# Voice.net
KiCad netlist of a schematic drawn in Altium Designer
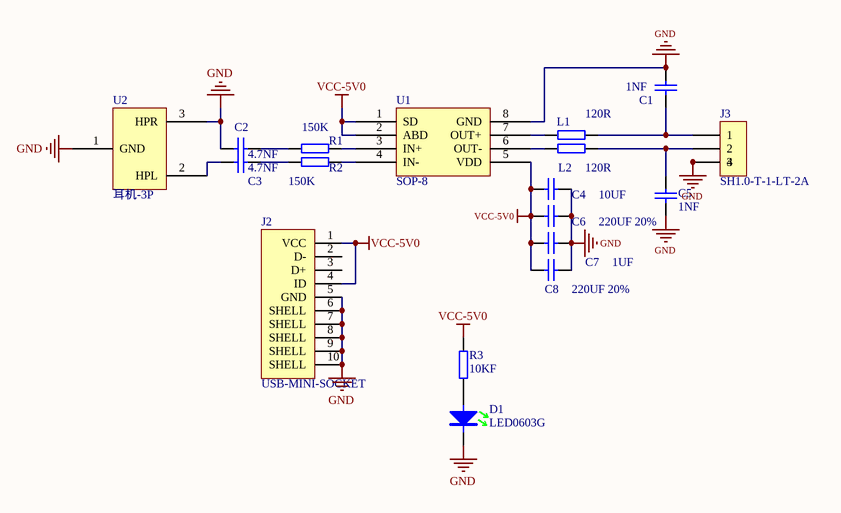
[diagram p0: Voice.SchDoc]

(export (version "E")
  (design (tool "Eeschema 10.0.6"))
  (components
    (comp (ref "C1")
      (value "1NF")
      (footprint "C0402")
      (description "贴片电容-陶瓷")
      (libsource (lib "Capacitor") (part "C0402X7R-220J10V"))
    )
    (comp (ref "C2")
      (value "4.7NF")
      (footprint "C0603")
      (description "贴片电容-陶瓷")
      (libsource (lib "Capacitor") (part "C0603X7R-330J25V"))
    )
    (comp (ref "C3")
      (value "4.7NF")
      (footprint "C0603")
      (description "贴片电容-陶瓷")
      (libsource (lib "Capacitor") (part "C0603X7R-330J25V"))
    )
    (comp (ref "C4")
      (value "10UF")
      (footprint "C0603")
      (description "贴片电容-陶瓷")
      (libsource (lib "Capacitor") (part "C0603X7R-330J25V"))
    )
    (comp (ref "C5")
      (value "1NF")
      (footprint "C0402")
      (description "贴片电容-陶瓷")
      (libsource (lib "Capacitor") (part "C0402X7R-220J10V"))
    )
    (comp (ref "C6")
      (value "220UF 20%")
      (footprint "C1206")
      (description "C 1206钽电容 --220UF 10V 3216 A型 有极性电容 3.2mm X 1.6mm")
      (libsource (lib "Capacitor") (part "C1206-A型 极性电容"))
    )
    (comp (ref "C7")
      (value "1UF")
      (footprint "C0402")
      (description "贴片电容-陶瓷")
      (libsource (lib "Capacitor") (part "C0402X7R-105J10V"))
    )
    (comp (ref "C8")
      (value "220UF 20%")
      (footprint "C1206")
      (description "C 1206钽电容 --220UF 10V 3216 A型 有极性电容 3.2mm X 1.6mm")
      (libsource (lib "Capacitor") (part "C1206-A型 极性电容"))
    )
    (comp (ref "D1")
      (value "LED0603G")
      (footprint "D-LED0603G")
      (description "贴片二极管-LED")
      (libsource (lib "PCB_Project_1") (part "DLED-0603-G"))
    )
    (comp (ref "J2")
      (value "USB-MINI-SOCKET")
      (footprint "MICRO-USB - 5.9")
      (description "USB-A卧式插座")
      (libsource (lib "PCB_Project_1") (part "J-USB-MINI-SOCKET"))
    )
    (comp (ref "J3")
      (value "SH1.0-T-1-LT-2A")
      (footprint "J-SH1.0-T-1-LT-2A")
      (description "接插件-SH1.0-T-1-LT-2A")
      (libsource (lib "Connector") (part "SH1.0-T-1-LT-2A"))
    )
    (comp (ref "L1")
      (value "120R")
      (footprint "R0603")
      (description "贴片电阻-通用")
      (libsource (lib "Resistor") (part "R0603-47KF"))
    )
    (comp (ref "L2")
      (value "120R")
      (footprint "R0603")
      (description "贴片电阻-通用")
      (libsource (lib "Resistor") (part "R0603-47KF"))
    )
    (comp (ref "R1")
      (value "150K")
      (footprint "R0603")
      (description "贴片电阻-通用")
      (libsource (lib "Resistor") (part "R0603-10KF"))
    )
    (comp (ref "R2")
      (value "150K")
      (footprint "R0603")
      (description "贴片电阻-通用")
      (libsource (lib "Resistor") (part "R0603-10KF"))
    )
    (comp (ref "R3")
      (value "10KF")
      (footprint "R0603")
      (description "贴片电阻-通用")
      (libsource (lib "PCB_Project_1") (part "R0603-10KF"))
    )
    (comp (ref "U1") (value "SOP-8") (footprint "SOP-8") (libsource (lib "PCB_Project_1") (part "CS8508E")))
    (comp (ref "U2") (value "耳机-3P") (footprint "耳机") (libsource (lib "PCB_Project_1") (part "耳机-3P")))
  )
  (nets
    (net (code "1") (name "GND") (class "Default")
      (node (ref "C1") (pin "2") (pinfunction "2_2") (pintype "passive"))
      (node (ref "C2") (pin "1") (pinfunction "1_1") (pintype "passive"))
      (node (ref "C4") (pin "2") (pinfunction "2_2") (pintype "passive"))
      (node (ref "C5") (pin "2") (pinfunction "2_2") (pintype "passive"))
      (node (ref "C6") (pin "1") (pinfunction "1_1") (pintype "passive"))
      (node (ref "C7") (pin "1") (pinfunction "1_1") (pintype "passive"))
      (node (ref "C8") (pin "1") (pinfunction "1_1") (pintype "passive"))
      (node (ref "D1") (pin "2") (pinfunction "2_2") (pintype "passive"))
      (node (ref "J2") (pin "10") (pinfunction "SHELL_10") (pintype "passive"))
      (node (ref "J2") (pin "5") (pinfunction "GND_5") (pintype "passive"))
      (node (ref "J2") (pin "6") (pinfunction "SHELL_6") (pintype "passive"))
      (node (ref "J2") (pin "7") (pinfunction "SHELL_7") (pintype "passive"))
      (node (ref "J2") (pin "8") (pinfunction "SHELL_8") (pintype "passive"))
      (node (ref "J2") (pin "9") (pinfunction "SHELL_9") (pintype "passive"))
      (node (ref "J3") (pin "3") (pinfunction "3_3") (pintype "passive"))
      (node (ref "J3") (pin "4") (pinfunction "4_4") (pintype "passive"))
      (node (ref "U1") (pin "8") (pinfunction "GND_8") (pintype "passive"))
      (node (ref "U2") (pin "1") (pinfunction "GND_1") (pintype "power_in"))
      (node (ref "U2") (pin "3") (pinfunction "HPR_3") (pintype "power_in"))
    )
    (net (code "2") (name "Net-(C1-Pad1)") (class "Default")
      (node (ref "C1") (pin "1") (pinfunction "1_1") (pintype "passive"))
      (node (ref "J3") (pin "1") (pinfunction "1_1") (pintype "passive"))
      (node (ref "L1") (pin "1") (pinfunction "1_1") (pintype "passive"))
    )
    (net (code "3") (name "Net-(C2-Pad2)") (class "Default")
      (node (ref "C2") (pin "2") (pinfunction "2_2") (pintype "passive"))
      (node (ref "R1") (pin "1") (pinfunction "1_1") (pintype "passive"))
    )
    (net (code "4") (name "Net-(C3-Pad2)") (class "Default")
      (node (ref "C3") (pin "2") (pinfunction "2_2") (pintype "passive"))
      (node (ref "R2") (pin "1") (pinfunction "1_1") (pintype "passive"))
    )
    (net (code "5") (name "Net-(C5-Pad1)") (class "Default")
      (node (ref "C5") (pin "1") (pinfunction "1_1") (pintype "passive"))
      (node (ref "J3") (pin "2") (pinfunction "2_2") (pintype "passive"))
      (node (ref "L2") (pin "1") (pinfunction "1_1") (pintype "passive"))
    )
    (net (code "6") (name "Net-(D1-Pad1)") (class "Default")
      (node (ref "D1") (pin "1") (pinfunction "1_1") (pintype "passive"))
      (node (ref "R3") (pin "1") (pinfunction "1_1") (pintype "passive"))
    )
    (net (code "7") (name "Net-(U1-IN+)") (class "Default")
      (node (ref "R1") (pin "2") (pinfunction "2_2") (pintype "passive"))
      (node (ref "U1") (pin "3") (pinfunction "IN+_3") (pintype "passive"))
    )
    (net (code "8") (name "Net-(U1-IN-)") (class "Default")
      (node (ref "R2") (pin "2") (pinfunction "2_2") (pintype "passive"))
      (node (ref "U1") (pin "4") (pinfunction "IN-_4") (pintype "passive"))
    )
    (net (code "9") (name "Net-(U1-OUT+)") (class "Default")
      (node (ref "L1") (pin "2") (pinfunction "2_2") (pintype "passive"))
      (node (ref "U1") (pin "7") (pinfunction "OUT+_7") (pintype "passive"))
    )
    (net (code "10") (name "Net-(U1-OUT-)") (class "Default")
      (node (ref "L2") (pin "2") (pinfunction "2_2") (pintype "passive"))
      (node (ref "U1") (pin "6") (pinfunction "OUT-_6") (pintype "passive"))
    )
    (net (code "11") (name "Net-(U2-HPL)") (class "Default")
      (node (ref "C3") (pin "1") (pinfunction "1_1") (pintype "passive"))
      (node (ref "U2") (pin "2") (pinfunction "HPL_2") (pintype "power_in"))
    )
    (net (code "12") (name "VCC-5V0") (class "Default")
      (node (ref "C4") (pin "1") (pinfunction "1_1") (pintype "passive"))
      (node (ref "C6") (pin "2") (pinfunction "2_2") (pintype "passive"))
      (node (ref "C7") (pin "2") (pinfunction "2_2") (pintype "passive"))
      (node (ref "C8") (pin "2") (pinfunction "2_2") (pintype "passive"))
      (node (ref "J2") (pin "1") (pinfunction "VCC_1") (pintype "passive"))
      (node (ref "J2") (pin "4") (pinfunction "ID_4") (pintype "passive"))
      (node (ref "R3") (pin "2") (pinfunction "2_2") (pintype "passive"))
      (node (ref "U1") (pin "1") (pinfunction "SD_1") (pintype "passive"))
      (node (ref "U1") (pin "2") (pinfunction "ABD_2") (pintype "passive"))
      (node (ref "U1") (pin "5") (pinfunction "VDD_5") (pintype "passive"))
    )
    (net (code "13") (name "unconnected-(J2-D+-Pad3)") (class "Default")
      (node (ref "J2") (pin "3") (pinfunction "D+_3") (pintype "passive"))
    )
    (net (code "14") (name "unconnected-(J2-D--Pad2)") (class "Default")
      (node (ref "J2") (pin "2") (pinfunction "D-_2") (pintype "passive"))
    )
  )
)
